# STM32_Smart.net
KiCad netlist of a schematic drawn in Altium Designer
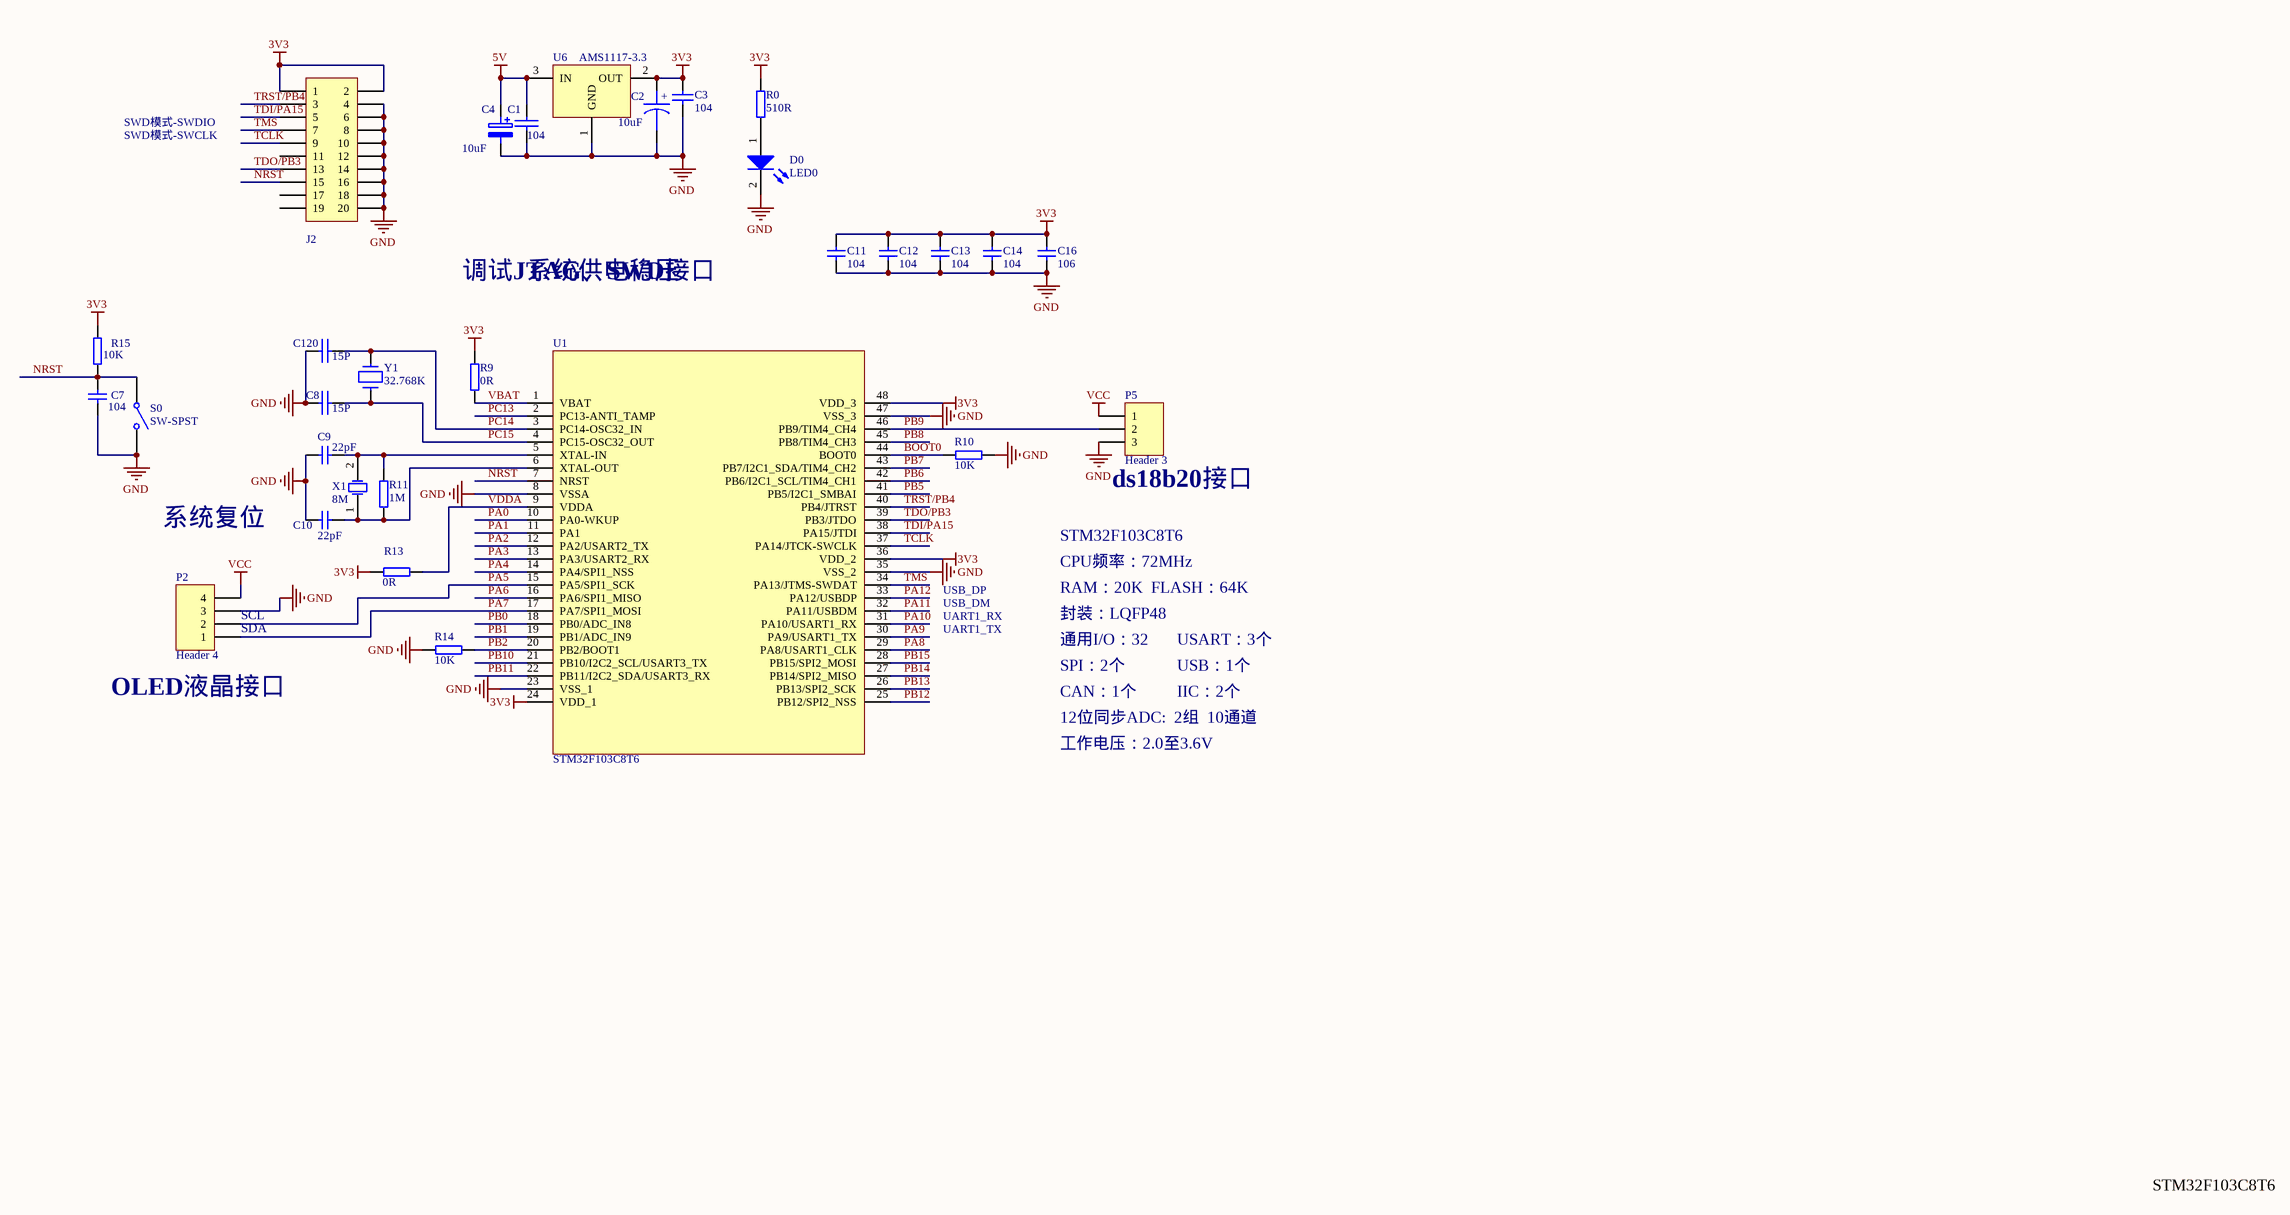
[diagram p0: STM32_Smart.SchDoc]

(export (version "E")
  (design (tool "Eeschema 10.0.6"))
  (components
    (comp (ref "C1")
      (value "104")
      (footprint "RC0603")
      (description "Capacitor")
      (libsource (lib "") (part "CAP_1"))
    )
    (comp (ref "C2")
      (value "10uF")
      (footprint "RC0805")
      (description "Capacitor")
      (libsource (lib "*") (part "CAPACITOR POL"))
    )
    (comp (ref "C3")
      (value "104")
      (footprint "RC0603")
      (description "Capacitor")
      (fields (field (name "PUBLISHER") "Altium Limited"))
      (libsource (lib "*") (part "Cap"))
    )
    (comp (ref "C4") (value "10uF") (footprint "RC0805") (libsource (lib "*") (part "ELECTRO2")))
    (comp (ref "C7")
      (value "104")
      (footprint "RC0603")
      (description "Capacitor")
      (fields (field (name "PUBLISHER") "ZL_A0OFFICE"))
      (libsource (lib "CommomDevices") (part "CAP1"))
    )
    (comp (ref "C8") (value "15P") (footprint "RC0603") (libsource (lib "*") (part "CAP")))
    (comp (ref "C9")
      (value "22pF")
      (footprint "RC0603")
      (description "Capacitor")
      (fields (field (name "PUBLISHER") "ZL_A0OFFICE"))
      (libsource (lib "CommomDevices") (part "CAP1"))
    )
    (comp (ref "C10")
      (value "22pF")
      (footprint "RC0603")
      (description "Capacitor")
      (fields (field (name "PUBLISHER") "ZL_A0OFFICE"))
      (libsource (lib "CommomDevices") (part "CAP1"))
    )
    (comp (ref "C11")
      (value "104")
      (footprint "RC0603")
      (description "Capacitor")
      (fields (field (name "PUBLISHER") "ZL_A0OFFICE"))
      (libsource (lib "CommomDevices") (part "CAP1"))
    )
    (comp (ref "C12")
      (value "104")
      (footprint "RC0603")
      (description "Capacitor")
      (fields (field (name "PUBLISHER") "ZL_A0OFFICE"))
      (libsource (lib "CommomDevices") (part "CAP1"))
    )
    (comp (ref "C13")
      (value "104")
      (footprint "RC0603")
      (description "Capacitor")
      (fields (field (name "PUBLISHER") "ZL_A0OFFICE"))
      (libsource (lib "CommomDevices") (part "CAP1"))
    )
    (comp (ref "C14")
      (value "104")
      (footprint "RC0603")
      (description "Capacitor")
      (fields (field (name "PUBLISHER") "ZL_A0OFFICE"))
      (libsource (lib "CommomDevices") (part "CAP1"))
    )
    (comp (ref "C16")
      (value "106")
      (footprint "RC0805")
      (description "Capacitor")
      (fields (field (name "PUBLISHER") "ZL_A0OFFICE"))
      (libsource (lib "CommomDevices") (part "CAP1"))
    )
    (comp (ref "C120") (value "15P") (footprint "RC0603") (libsource (lib "*") (part "CAP")))
    (comp (ref "D0")
      (value "LED0")
      (footprint "LED0805")
      (description "Typical INFRARED GaAs LED")
      (libsource (lib "Miscellaneous Devices") (part "LED0"))
    )
    (comp (ref "J2")
      (value "~")
      (footprint "JTAG20P")
      (description "Header, 10-Pin, Dual row, Right Angle")
      (fields (field (name "PUBLISHER") "Altium Limited"))
      (libsource (lib "Miscellaneous Connectors") (part "Header 10X2H"))
    )
    (comp (ref "P2")
      (value "Header 4")
      (footprint "HDR1X4")
      (description "Header, 4-Pin")
      (fields (field (name "PUBLISHER") "Altium Limited"))
      (libsource (lib "Miscellaneous Connectors") (part "Header 4"))
    )
    (comp (ref "P5")
      (value "Header 3")
      (footprint "HDR1X3")
      (description "Header, 3-Pin")
      (fields (field (name "PUBLISHER") "Altium Limited"))
      (libsource (lib "Miscellaneous Connectors") (part "Header 3"))
    )
    (comp (ref "R0") (value "510R") (footprint "RC0603") (libsource (lib "ZIBO V2.0_Main") (part "R")))
    (comp (ref "R9") (value "0R") (footprint "RC0603") (libsource (lib "ZIBO V2.0_Main") (part "R")))
    (comp (ref "R10") (value "10K") (footprint "RC0603") (libsource (lib "ZIBO V2.0_Main") (part "R")))
    (comp (ref "R11") (value "1M") (footprint "RC0603") (libsource (lib "ZIBO V2.0_Main") (part "R")))
    (comp (ref "R13") (value "0R") (footprint "RC0603") (libsource (lib "ZIBO V2.0_Main") (part "R")))
    (comp (ref "R14") (value "10K") (footprint "RC0603") (libsource (lib "ZIBO V2.0_Main") (part "R")))
    (comp (ref "R15") (value "10K") (footprint "RC0603") (libsource (lib "ZIBO V2.0_Main") (part "R")))
    (comp (ref "S0")
      (value "SW-SPST")
      (footprint "SMT-KEY")
      (description "Single-Pole, Single-Throw Switch")
      (libsource (lib "Miscellaneous Devices") (part "SW-SPST"))
    )
    (comp (ref "U1")
      (value "STM32F103C8T6")
      (footprint "LQFP48")
      (libsource (lib "STM32_Smart") (part "STM32F103C8T6"))
    )
    (comp (ref "U6")
      (value "AMS1117-3.3")
      (footprint "SOT223")
      (libsource (lib "Newcapec9263_Board_NEW") (part "LT1085CM-3.3"))
    )
    (comp (ref "X1")
      (value "8M")
      (footprint "SMD49S")
      (description "Crystal Oscillator")
      (fields (field (name "PUBLISHER") "ZL_A0OFFICE"))
      (libsource (lib "CommomDevices") (part "XTAL_SMD"))
    )
    (comp (ref "Y1")
      (value "32.768K")
      (footprint "JZ32768")
      (description "晶振")
      (libsource (lib "*") (part "CRYSTAL"))
    )
  )
  (nets
    (net (code "1") (name "/BOOT0") (class "Default")
      (node (ref "R10") (pin "2") (pinfunction "2_2") (pintype "passive"))
      (node (ref "U1") (pin "44") (pinfunction "BOOT0_44") (pintype "passive"))
    )
    (net (code "2") (name "/NRST") (class "Default")
      (node (ref "C7") (pin "1") (pinfunction "1_1") (pintype "passive"))
      (node (ref "J2") (pin "15") (pinfunction "15_15") (pintype "passive"))
      (node (ref "R15") (pin "1") (pinfunction "1_1") (pintype "passive"))
      (node (ref "S0") (pin "1") (pinfunction "COMMON_1") (pintype "passive"))
      (node (ref "U1") (pin "7") (pinfunction "NRST_7") (pintype "passive"))
    )
    (net (code "3") (name "/PA0") (class "Default")
      (node (ref "U1") (pin "10") (pinfunction "PA0-WKUP_10") (pintype "passive"))
    )
    (net (code "4") (name "/PA1") (class "Default")
      (node (ref "U1") (pin "11") (pinfunction "PA1_11") (pintype "passive"))
    )
    (net (code "5") (name "/PA2") (class "Default")
      (node (ref "U1") (pin "12") (pinfunction "PA2/USART2_TX_12") (pintype "passive"))
    )
    (net (code "6") (name "/PA3") (class "Default")
      (node (ref "U1") (pin "13") (pinfunction "PA3/USART2_RX_13") (pintype "passive"))
    )
    (net (code "7") (name "/PA4") (class "Default")
      (node (ref "U1") (pin "14") (pinfunction "PA4/SPI1_NSS_14") (pintype "passive"))
    )
    (net (code "8") (name "/PA5") (class "Default")
      (node (ref "P2") (pin "2") (pinfunction "2_2") (pintype "passive"))
      (node (ref "U1") (pin "15") (pinfunction "PA5/SPI1_SCK_15") (pintype "passive"))
    )
    (net (code "9") (name "/PA6") (class "Default")
      (node (ref "U1") (pin "16") (pinfunction "PA6/SPI1_MISO_16") (pintype "passive"))
    )
    (net (code "10") (name "/PA7") (class "Default")
      (node (ref "P2") (pin "1") (pinfunction "1_1") (pintype "passive"))
      (node (ref "U1") (pin "17") (pinfunction "PA7/SPI1_MOSI_17") (pintype "passive"))
    )
    (net (code "11") (name "/PA8") (class "Default")
      (node (ref "U1") (pin "29") (pinfunction "PA8/USART1_CLK_29") (pintype "passive"))
    )
    (net (code "12") (name "/PA9") (class "Default")
      (node (ref "U1") (pin "30") (pinfunction "PA9/USART1_TX_30") (pintype "passive"))
    )
    (net (code "13") (name "/PA10") (class "Default")
      (node (ref "U1") (pin "31") (pinfunction "PA10/USART1_RX_31") (pintype "passive"))
    )
    (net (code "14") (name "/PA11") (class "Default")
      (node (ref "U1") (pin "32") (pinfunction "PA11/USBDM_32") (pintype "passive"))
    )
    (net (code "15") (name "/PA12") (class "Default")
      (node (ref "U1") (pin "33") (pinfunction "PA12/USBDP_33") (pintype "passive"))
    )
    (net (code "16") (name "/PB0") (class "Default")
      (node (ref "U1") (pin "18") (pinfunction "PB0/ADC_IN8_18") (pintype "passive"))
    )
    (net (code "17") (name "/PB1") (class "Default")
      (node (ref "U1") (pin "19") (pinfunction "PB1/ADC_IN9_19") (pintype "passive"))
    )
    (net (code "18") (name "/PB2") (class "Default")
      (node (ref "R14") (pin "1") (pinfunction "1_1") (pintype "passive"))
      (node (ref "U1") (pin "20") (pinfunction "PB2/BOOT1_20") (pintype "passive"))
    )
    (net (code "19") (name "/PB5") (class "Default")
      (node (ref "U1") (pin "41") (pinfunction "PB5/I2C1_SMBAI_41") (pintype "passive"))
    )
    (net (code "20") (name "/PB6") (class "Default")
      (node (ref "U1") (pin "42") (pinfunction "PB6/I2C1_SCL/TIM4_CH1_42") (pintype "passive"))
    )
    (net (code "21") (name "/PB7") (class "Default")
      (node (ref "U1") (pin "43") (pinfunction "PB7/I2C1_SDA/TIM4_CH2_43") (pintype "passive"))
    )
    (net (code "22") (name "/PB8") (class "Default")
      (node (ref "U1") (pin "45") (pinfunction "PB8/TIM4_CH3_45") (pintype "passive"))
    )
    (net (code "23") (name "/PB9") (class "Default")
      (node (ref "P5") (pin "2") (pinfunction "2_2") (pintype "passive"))
      (node (ref "U1") (pin "46") (pinfunction "PB9/TIM4_CH4_46") (pintype "passive"))
    )
    (net (code "24") (name "/PB10") (class "Default")
      (node (ref "U1") (pin "21") (pinfunction "PB10/I2C2_SCL/USART3_TX_21") (pintype "passive"))
    )
    (net (code "25") (name "/PB11") (class "Default")
      (node (ref "U1") (pin "22") (pinfunction "PB11/I2C2_SDA/USART3_RX_22") (pintype "passive"))
    )
    (net (code "26") (name "/PB12") (class "Default")
      (node (ref "U1") (pin "25") (pinfunction "PB12/SPI2_NSS_25") (pintype "passive"))
    )
    (net (code "27") (name "/PB13") (class "Default")
      (node (ref "U1") (pin "26") (pinfunction "PB13/SPI2_SCK_26") (pintype "passive"))
    )
    (net (code "28") (name "/PB14") (class "Default")
      (node (ref "U1") (pin "27") (pinfunction "PB14/SPI2_MISO_27") (pintype "passive"))
    )
    (net (code "29") (name "/PB15") (class "Default")
      (node (ref "U1") (pin "28") (pinfunction "PB15/SPI2_MOSI_28") (pintype "passive"))
    )
    (net (code "30") (name "/PC13") (class "Default")
      (node (ref "U1") (pin "2") (pinfunction "PC13-ANTI_TAMP_2") (pintype "passive"))
    )
    (net (code "31") (name "/PC14") (class "Default")
      (node (ref "C120") (pin "2") (pintype "passive"))
      (node (ref "U1") (pin "3") (pinfunction "PC14-OSC32_IN_3") (pintype "passive"))
      (node (ref "Y1") (pin "2") (pintype "passive"))
    )
    (net (code "32") (name "/PC15") (class "Default")
      (node (ref "C8") (pin "2") (pintype "passive"))
      (node (ref "U1") (pin "4") (pinfunction "PC15-OSC32_OUT_4") (pintype "passive"))
      (node (ref "Y1") (pin "1") (pintype "passive"))
    )
    (net (code "33") (name "/TCLK") (class "Default")
      (node (ref "J2") (pin "9") (pinfunction "9_9") (pintype "passive"))
      (node (ref "U1") (pin "37") (pinfunction "PA14/JTCK-SWCLK_37") (pintype "passive"))
    )
    (net (code "34") (name "/TDI{slash}PA15") (class "Default")
      (node (ref "J2") (pin "5") (pinfunction "5_5") (pintype "passive"))
      (node (ref "U1") (pin "38") (pinfunction "PA15/JTDI_38") (pintype "passive"))
    )
    (net (code "35") (name "/TDO{slash}PB3") (class "Default")
      (node (ref "J2") (pin "13") (pinfunction "13_13") (pintype "passive"))
      (node (ref "U1") (pin "39") (pinfunction "PB3/JTDO_39") (pintype "passive"))
    )
    (net (code "36") (name "/TMS") (class "Default")
      (node (ref "J2") (pin "7") (pinfunction "7_7") (pintype "passive"))
      (node (ref "U1") (pin "34") (pinfunction "PA13/JTMS-SWDAT_34") (pintype "passive"))
    )
    (net (code "37") (name "/TRST{slash}PB4") (class "Default")
      (node (ref "J2") (pin "3") (pinfunction "3_3") (pintype "passive"))
      (node (ref "U1") (pin "40") (pinfunction "PB4/JTRST_40") (pintype "passive"))
    )
    (net (code "38") (name "/VBAT") (class "Default")
      (node (ref "R9") (pin "1") (pinfunction "1_1") (pintype "passive"))
      (node (ref "U1") (pin "1") (pinfunction "VBAT_1") (pintype "passive"))
    )
    (net (code "39") (name "/VDDA") (class "Default")
      (node (ref "R13") (pin "1") (pinfunction "1_1") (pintype "passive"))
      (node (ref "U1") (pin "9") (pinfunction "VDDA_9") (pintype "passive"))
    )
    (net (code "40") (name "3V3") (class "Default")
      (node (ref "C11") (pin "1") (pinfunction "1_1") (pintype "passive"))
      (node (ref "C12") (pin "1") (pinfunction "1_1") (pintype "passive"))
      (node (ref "C13") (pin "1") (pinfunction "1_1") (pintype "passive"))
      (node (ref "C14") (pin "1") (pinfunction "1_1") (pintype "passive"))
      (node (ref "C16") (pin "1") (pinfunction "1_1") (pintype "passive"))
      (node (ref "C2") (pin "1") (pinfunction "1_1") (pintype "passive"))
      (node (ref "C3") (pin "1") (pinfunction "1_1") (pintype "passive"))
      (node (ref "J2") (pin "1") (pinfunction "1_1") (pintype "passive"))
      (node (ref "J2") (pin "2") (pinfunction "2_2") (pintype "passive"))
      (node (ref "R0") (pin "2") (pinfunction "2_2") (pintype "passive"))
      (node (ref "R13") (pin "2") (pinfunction "2_2") (pintype "passive"))
      (node (ref "R15") (pin "2") (pinfunction "2_2") (pintype "passive"))
      (node (ref "R9") (pin "2") (pinfunction "2_2") (pintype "passive"))
      (node (ref "U1") (pin "24") (pinfunction "VDD_1_24") (pintype "passive"))
      (node (ref "U1") (pin "36") (pinfunction "VDD_2_36") (pintype "passive"))
      (node (ref "U1") (pin "48") (pinfunction "VDD_3_48") (pintype "passive"))
      (node (ref "U6") (pin "2") (pinfunction "OUT_2") (pintype "passive"))
    )
    (net (code "41") (name "5V") (class "Default")
      (node (ref "C1") (pin "1") (pinfunction "1_1") (pintype "passive"))
      (node (ref "C4") (pin "1") (pintype "passive"))
      (node (ref "U6") (pin "3") (pinfunction "IN_3") (pintype "passive"))
    )
    (net (code "42") (name "GND") (class "Default")
      (node (ref "C1") (pin "2") (pinfunction "2_2") (pintype "passive"))
      (node (ref "C10") (pin "2") (pinfunction "2_2") (pintype "passive"))
      (node (ref "C11") (pin "2") (pinfunction "2_2") (pintype "passive"))
      (node (ref "C12") (pin "2") (pinfunction "2_2") (pintype "passive"))
      (node (ref "C120") (pin "1") (pintype "passive"))
      (node (ref "C13") (pin "2") (pinfunction "2_2") (pintype "passive"))
      (node (ref "C14") (pin "2") (pinfunction "2_2") (pintype "passive"))
      (node (ref "C16") (pin "2") (pinfunction "2_2") (pintype "passive"))
      (node (ref "C2") (pin "2") (pinfunction "2_2") (pintype "passive"))
      (node (ref "C3") (pin "2") (pinfunction "2_2") (pintype "passive"))
      (node (ref "C4") (pin "2") (pintype "passive"))
      (node (ref "C7") (pin "2") (pinfunction "2_2") (pintype "passive"))
      (node (ref "C8") (pin "1") (pintype "passive"))
      (node (ref "C9") (pin "2") (pinfunction "2_2") (pintype "passive"))
      (node (ref "D0") (pin "2") (pinfunction "K_2") (pintype "passive"))
      (node (ref "J2") (pin "10") (pinfunction "10_10") (pintype "passive"))
      (node (ref "J2") (pin "12") (pinfunction "12_12") (pintype "passive"))
      (node (ref "J2") (pin "14") (pinfunction "14_14") (pintype "passive"))
      (node (ref "J2") (pin "16") (pinfunction "16_16") (pintype "passive"))
      (node (ref "J2") (pin "18") (pinfunction "18_18") (pintype "passive"))
      (node (ref "J2") (pin "20") (pinfunction "20_20") (pintype "passive"))
      (node (ref "J2") (pin "4") (pinfunction "4_4") (pintype "passive"))
      (node (ref "J2") (pin "6") (pinfunction "6_6") (pintype "passive"))
      (node (ref "J2") (pin "8") (pinfunction "8_8") (pintype "passive"))
      (node (ref "P2") (pin "3") (pinfunction "3_3") (pintype "passive"))
      (node (ref "P5") (pin "3") (pinfunction "3_3") (pintype "passive"))
      (node (ref "R10") (pin "1") (pinfunction "1_1") (pintype "passive"))
      (node (ref "R14") (pin "2") (pinfunction "2_2") (pintype "passive"))
      (node (ref "S0") (pin "2") (pinfunction "NO_2") (pintype "passive"))
      (node (ref "U1") (pin "23") (pinfunction "VSS_1_23") (pintype "passive"))
      (node (ref "U1") (pin "35") (pinfunction "VSS_2_35") (pintype "passive"))
      (node (ref "U1") (pin "47") (pinfunction "VSS_3_47") (pintype "passive"))
      (node (ref "U1") (pin "8") (pinfunction "VSSA_8") (pintype "passive"))
      (node (ref "U6") (pin "1") (pinfunction "GND_1") (pintype "passive"))
    )
    (net (code "43") (name "Net-(D0-A)") (class "Default")
      (node (ref "D0") (pin "1") (pinfunction "A_1") (pintype "passive"))
      (node (ref "R0") (pin "1") (pinfunction "1_1") (pintype "passive"))
    )
    (net (code "44") (name "Net-(U1-XTAL-IN)") (class "Default")
      (node (ref "C9") (pin "1") (pinfunction "1_1") (pintype "passive"))
      (node (ref "R11") (pin "2") (pinfunction "2_2") (pintype "passive"))
      (node (ref "U1") (pin "5") (pinfunction "XTAL-IN_5") (pintype "passive"))
      (node (ref "X1") (pin "2") (pinfunction "2_2") (pintype "passive"))
    )
    (net (code "45") (name "Net-(U1-XTAL-OUT)") (class "Default")
      (node (ref "C10") (pin "1") (pinfunction "1_1") (pintype "passive"))
      (node (ref "R11") (pin "1") (pinfunction "1_1") (pintype "passive"))
      (node (ref "U1") (pin "6") (pinfunction "XTAL-OUT_6") (pintype "passive"))
      (node (ref "X1") (pin "1") (pinfunction "1_1") (pintype "passive"))
    )
    (net (code "46") (name "VCC") (class "Default")
      (node (ref "P2") (pin "4") (pinfunction "4_4") (pintype "passive"))
      (node (ref "P5") (pin "1") (pinfunction "1_1") (pintype "passive"))
    )
    (net (code "47") (name "unconnected-(J2-Pad11)") (class "Default")
      (node (ref "J2") (pin "11") (pinfunction "11_11") (pintype "passive"))
    )
    (net (code "48") (name "unconnected-(J2-Pad17)") (class "Default")
      (node (ref "J2") (pin "17") (pinfunction "17_17") (pintype "passive"))
    )
    (net (code "49") (name "unconnected-(J2-Pad19)") (class "Default")
      (node (ref "J2") (pin "19") (pinfunction "19_19") (pintype "passive"))
    )
  )
)
